# LV_Power.net
KiCad netlist of a schematic drawn in Altium Designer
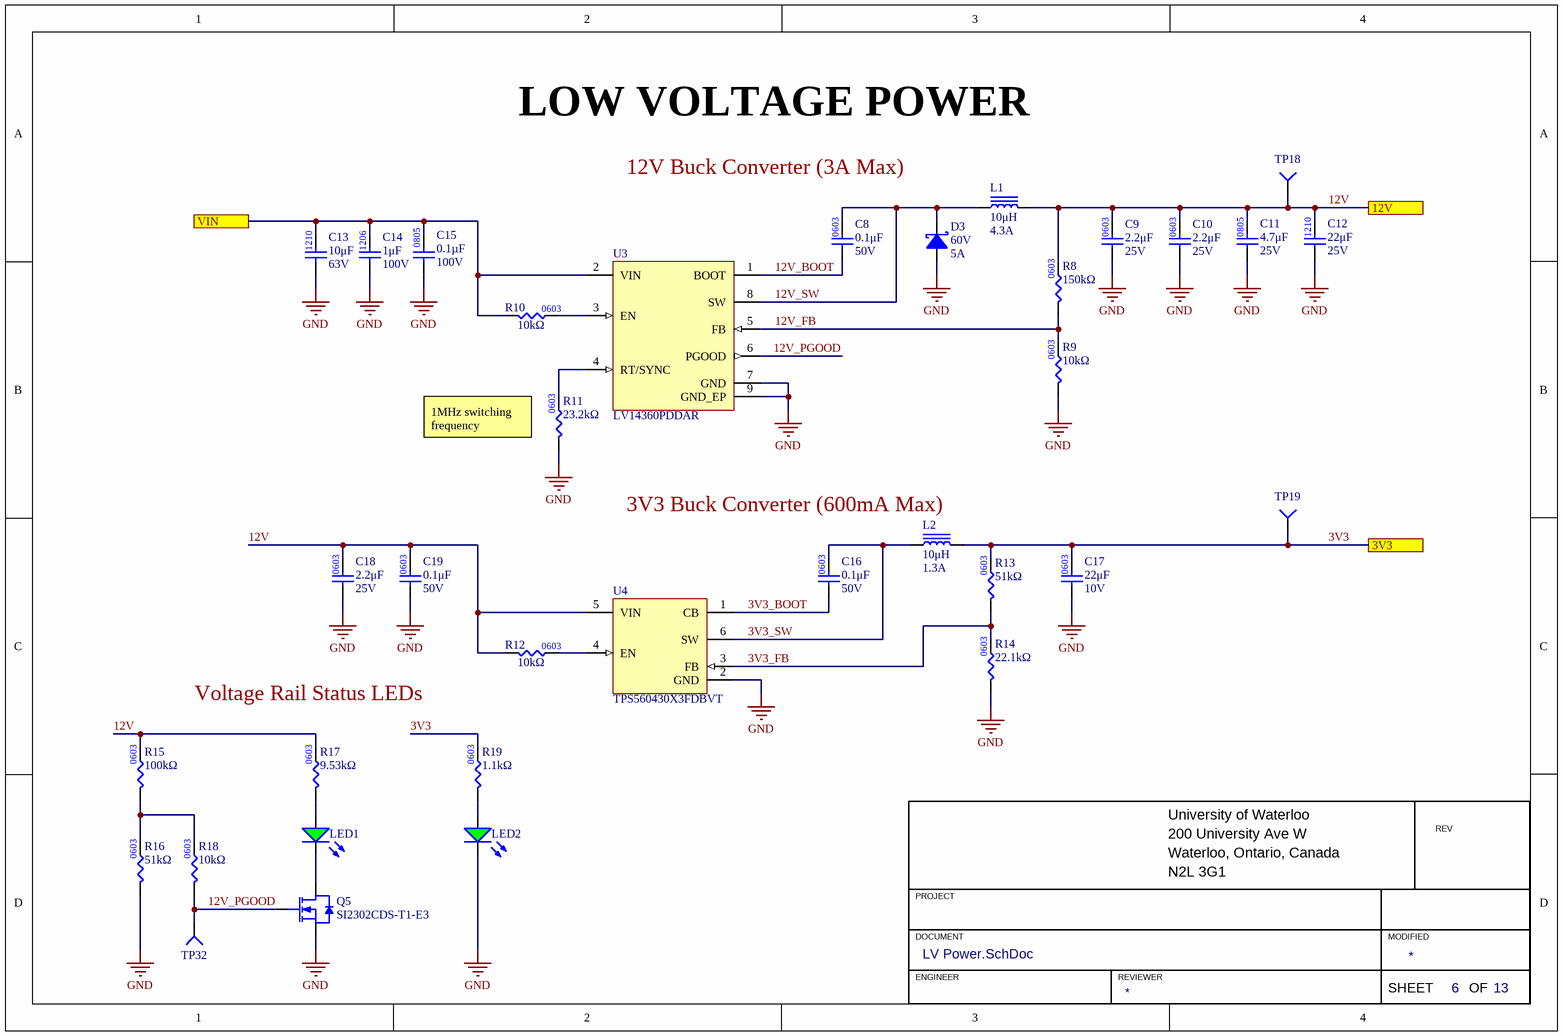
[diagram p0: LV Power.SchDoc]

(export (version "E")
  (design (tool "Eeschema 10.0.6"))
  (components
    (comp (ref "C8")
      (value "0.1μF")
      (footprint "CAP0603")
      (description "CAP CER 0.1UF 50V X7R 0603")
      (fields (field (name "VOLTAGE RATING") "50V") (field (name "Comment") "CAP_0.1uF_50V_0603"))
      (libsource (lib "Personal_Schematic_Library_2022") (part "CAP_0.1uF_50V_0603"))
    )
    (comp (ref "C9")
      (value "2.2μF")
      (footprint "CAP0603")
      (description "CAP CER 2.2UF 25V X5R 0603")
      (fields (field (name "VOLTAGE RATING") "25V") (field (name "Comment") "CAP_2.2uF_25V_0603"))
      (libsource (lib "Personal_Schematic_Library_2022") (part "CAP_2.2uF_25V_0603"))
    )
    (comp (ref "C10")
      (value "2.2μF")
      (footprint "CAP0603")
      (description "CAP CER 2.2UF 25V X5R 0603")
      (fields (field (name "VOLTAGE RATING") "25V") (field (name "Comment") "CAP_2.2uF_25V_0603"))
      (libsource (lib "Personal_Schematic_Library_2022") (part "CAP_2.2uF_25V_0603"))
    )
    (comp (ref "C11")
      (value "4.7μF")
      (footprint "CAP0805")
      (description "CAP CER 4.7UF 25V X7R 0805")
      (fields (field (name "VOLTAGE RATING") "25V") (field (name "Comment") "CAP_4.7uF_25V_0805"))
      (libsource (lib "Personal_Schematic_Library_2022") (part "CAP_4.7uF_25V_0805"))
    )
    (comp (ref "C12")
      (value "22μF")
      (footprint "CAP1210")
      (description "CAP CER 22UF 25V X7R 1210")
      (fields (field (name "VOLTAGE RATING") "25V") (field (name "Comment") "CAP_22uF_25V_1210"))
      (libsource (lib "Personal_Schematic_Library_2022") (part "CAP_22uF_25V_1210"))
    )
    (comp (ref "C13")
      (value "10μF")
      (footprint "CAP1210")
      (description "CAP CER 10UF 63V X7R 1210")
      (fields (field (name "VOLTAGE RATING") "63V") (field (name "Comment") "CAP_10uF_63V_1210"))
      (libsource (lib "Personal_Schematic_Library_2022") (part "CAP_10uF_63V_1210"))
    )
    (comp (ref "C14")
      (value "1μF")
      (footprint "CAP1206")
      (description "CAP CER 1UF 100V X7R 1206")
      (fields (field (name "VOLTAGE RATING") "100V") (field (name "Comment") "CAP_1uF_100V_1206"))
      (libsource (lib "Personal_Schematic_Library_2022") (part "CAP_1uF_100V_1206"))
    )
    (comp (ref "C15")
      (value "0.1µF")
      (footprint "CAP0805")
      (description "CAP CER 0.1UF 100V X7R 0805")
      (fields (field (name "VOLTAGE RATING") "100V") (field (name "Comment") "CAP_0.1uF_100V_0805"))
      (libsource (lib "Personal_Schematic_Library_2022") (part "CAP_0.1uF_100V_0805"))
    )
    (comp (ref "C16")
      (value "0.1μF")
      (footprint "CAP0603")
      (description "CAP CER 0.1UF 50V X7R 0603")
      (fields (field (name "VOLTAGE RATING") "50V") (field (name "Comment") "CAP_0.1uF_50V_0603"))
      (libsource (lib "Personal_Schematic_Library_2022") (part "CAP_0.1uF_50V_0603"))
    )
    (comp (ref "C17")
      (value "22μF")
      (footprint "CAP0603")
      (description "CAP CER 22UF 10V X5R 0603")
      (fields
        (field (name "MANUFACTURER") "Taiyo Yuden")
        (field (name "MANUFACTURER PART NUMBER") "LMK107BBJ226MA-T")
        (field (name "VOLTAGE RATING") "10V")
      )
      (libsource (lib "Personal_Schematic_Library_2022") (part "CAP_22uF_10V_0603"))
    )
    (comp (ref "C18")
      (value "2.2μF")
      (footprint "CAP0603")
      (description "CAP CER 2.2UF 25V X5R 0603")
      (fields (field (name "VOLTAGE RATING") "25V") (field (name "Comment") "CAP_2.2uF_25V_0603"))
      (libsource (lib "Personal_Schematic_Library_2022") (part "CAP_2.2uF_25V_0603"))
    )
    (comp (ref "C19")
      (value "0.1μF")
      (footprint "CAP0603")
      (description "CAP CER 0.1UF 50V X7R 0603")
      (fields (field (name "VOLTAGE RATING") "50V") (field (name "Comment") "CAP_0.1uF_50V_0603"))
      (libsource (lib "Personal_Schematic_Library_2022") (part "CAP_0.1uF_50V_0603"))
    )
    (comp (ref "D3")
      (value "DIO_SCHOTTKY_60V_5A")
      (footprint "DIO-INC_SMA")
      (description "DIODE SCHOTTKY 60V 5A SMA")
      (fields (field (name "VR (MAX)") "60V") (field (name "CURRENT - AVERAGE RECTIFIED (IO)") "5A"))
      (libsource (lib "Personal_Schematic_Library_2022") (part "DIO_SCHOTTKY_60V_5A"))
    )
    (comp (ref "L1")
      (value "10μH")
      (footprint "IND_MURATA_DS106C2")
      (description "FIXED IND 10UH 4.3A 28 MOHM SMD")
      (fields (field (name "CURRENT RATING") "4.3A") (field (name "Comment") "IND_10uH_4.3A"))
      (libsource (lib "Personal_Schematic_Library_2022") (part "IND_10uH_4.3A"))
    )
    (comp (ref "L2")
      (value "10μH")
      (footprint "IND_ABRACON_ASPI4030S")
      (description "FIXED IND 12UH 1.3A 135 MOHM SMD")
      (fields (field (name "CURRENT RATING") "1.3A") (field (name "Comment") "IND_10uH_1.3A"))
      (libsource (lib "Personal_Schematic_Library_2022") (part "IND_10uH_1.3A"))
    )
    (comp (ref "LED1")
      (value "LED_GREEN_0805")
      (footprint "LED_0805_GREEN")
      (description "LED GREEN DIFFUSED 0805 SMD")
      (libsource (lib "Personal_Schematic_Library_2022") (part "LED_GREEN_0805"))
    )
    (comp (ref "LED2")
      (value "LED_GREEN_0805")
      (footprint "LED_0805_GREEN")
      (description "LED GREEN DIFFUSED 0805 SMD")
      (libsource (lib "Personal_Schematic_Library_2022") (part "LED_GREEN_0805"))
    )
    (comp (ref "Q5")
      (value "NMOS_20V_6A")
      (footprint "SOT23-3")
      (description "MOSFET N-CH 20V 2.6A SOT23-3")
      (fields (field (name "MANUFACTURER PART NUMBER 1") "SI2302CDS-T1-E3"))
      (libsource (lib "Personal_Schematic_Library_2022") (part "NMOS_20V_2.6A"))
    )
    (comp (ref "R8")
      (value "150kΩ")
      (footprint "RES0603")
      (description "RES 150K OHM 1% 1/10W 0603")
      (fields (field (name "Comment") "RES_150kΩ_0603_1%"))
      (libsource (lib "Personal_Schematic_Library_2022") (part "RES_150kΩ_0603_1%"))
    )
    (comp (ref "R9")
      (value "10kΩ")
      (footprint "RES0603")
      (description "RES 10K OHM 1% 1/8W 0603")
      (fields (field (name "Comment") "RES_10kΩ_0603_1%"))
      (libsource (lib "Personal_Schematic_Library_2022") (part "RES_10kΩ_0603_1%"))
    )
    (comp (ref "R10")
      (value "10kΩ")
      (footprint "RES0603")
      (description "RES 10K OHM 1% 1/8W 0603")
      (fields (field (name "Comment") "RES_10kΩ_0603_1%"))
      (libsource (lib "Personal_Schematic_Library_2022") (part "RES_10kΩ_0603_1%"))
    )
    (comp (ref "R11")
      (value "23.2kΩ")
      (footprint "RES0603")
      (description "RES 23.2K OHM 1% 1/10W 0603")
      (fields (field (name "Comment") "RES_23.2kΩ_0603_1%"))
      (libsource (lib "Personal_Schematic_Library_2022") (part "RES_23.2kΩ_0603_1%"))
    )
    (comp (ref "R12")
      (value "10kΩ")
      (footprint "RES0603")
      (description "RES 10K OHM 1% 1/8W 0603")
      (fields (field (name "Comment") "RES_10kΩ_0603_1%"))
      (libsource (lib "Personal_Schematic_Library_2022") (part "RES_10kΩ_0603_1%"))
    )
    (comp (ref "R13")
      (value "51kΩ")
      (footprint "RES0603")
      (description "RES 51K OHM 1% 1/10W 0603")
      (fields (field (name "Comment") "RES_51kΩ_0603_1%"))
      (libsource (lib "Personal_Schematic_Library_2022") (part "RES_51kΩ_0603_1%"))
    )
    (comp (ref "R14")
      (value "22.1kΩ")
      (footprint "RES0603")
      (description "RES 22.1K OHM 1% 1/10W 0603")
      (fields (field (name "Comment") "RES_22.1kΩ_0603_1%"))
      (libsource (lib "Personal_Schematic_Library_2022") (part "RES_22.1kΩ_0603_1%"))
    )
    (comp (ref "R15")
      (value "100kΩ")
      (footprint "RES0603")
      (description "RES 100K OHM 1% 1/10W 0603")
      (fields (field (name "Comment") "RES_100kΩ_0603_1%"))
      (libsource (lib "Personal_Schematic_Library_2022") (part "RES_100kΩ_0603_1%"))
    )
    (comp (ref "R16")
      (value "51kΩ")
      (footprint "RES0603")
      (description "RES 51K OHM 1% 1/10W 0603")
      (fields (field (name "Comment") "RES_51kΩ_0603_1%"))
      (libsource (lib "Personal_Schematic_Library_2022") (part "RES_51kΩ_0603_1%"))
    )
    (comp (ref "R17")
      (value "9.53kΩ")
      (footprint "RES0603")
      (description "RES 9.53K OHM 1% 1/10W 0603")
      (fields (field (name "Comment") "RES_9.53kΩ_0603_1%"))
      (libsource (lib "Personal_Schematic_Library_2022") (part "RES_9.53kΩ_0603_1%"))
    )
    (comp (ref "R18")
      (value "10kΩ")
      (footprint "RES0603")
      (description "RES 10K OHM 1% 1/8W 0603")
      (fields (field (name "Comment") "RES_10kΩ_0603_1%"))
      (libsource (lib "Personal_Schematic_Library_2022") (part "RES_10kΩ_0603_1%"))
    )
    (comp (ref "R19")
      (value "1.1kΩ")
      (footprint "RES0603")
      (description "RES 1.1K OHM 1% 1/10W 0603")
      (fields (field (name "Comment") "RES_1.1kΩ_0603_1%"))
      (libsource (lib "Personal_Schematic_Library_2022") (part "RES_1.1kΩ_0603_1%"))
    )
    (comp (ref "TP18")
      (value "TESTPOINT_KEYSTONE_LOOP")
      (footprint "KEYSTONE_5019")
      (description "PC TEST POINT MINIATURE")
      (libsource (lib "Personal_Schematic_Library_2022") (part "TESTPOINT_KEYSTONE_LOOP"))
    )
    (comp (ref "TP19")
      (value "TESTPOINT_KEYSTONE_LOOP")
      (footprint "KEYSTONE_5019")
      (description "PC TEST POINT MINIATURE")
      (libsource (lib "Personal_Schematic_Library_2022") (part "TESTPOINT_KEYSTONE_LOOP"))
    )
    (comp (ref "TP32")
      (value "TESTPOINT_1MM_CIRCLE")
      (footprint "TESTPOINT_CIRCLE_1MM")
      (description "TESTPOINT 1MM CIRCLE")
      (libsource (lib "Personal_Schematic_Library_2022") (part "TESTPOINT_1MM_CIRCLE"))
    )
    (comp (ref "U3")
      (value "LV14360PDDAR")
      (footprint "TI_8-PowerPad-SOIC")
      (description "IC REG BUCK ADJ 3A 8SOPWR")
      (libsource (lib "Personal_Schematic_Library_2022") (part "LV14360PDDAR"))
    )
    (comp (ref "U4")
      (value "TPS560430X3FDBVT")
      (footprint "SOT23-6")
      (description "IC REG BUCK 3.3V 600MA SOT23-6")
      (libsource (lib "Personal_Schematic_Library_2022") (part "TPS560430X3FDBVT"))
    )
  )
  (nets
    (net (code "1") (name "/3V3") (class "Default")
      (node (ref "C17") (pin "2") (pinfunction "2_2") (pintype "passive"))
      (node (ref "L2") (pin "2") (pinfunction "2_2") (pintype "passive"))
      (node (ref "R13") (pin "2") (pinfunction "2_2") (pintype "passive"))
      (node (ref "R19") (pin "2") (pinfunction "2_2") (pintype "passive"))
      (node (ref "TP19") (pin "1") (pinfunction "=value_1") (pintype "passive"))
    )
    (net (code "2") (name "/3V3_BOOT") (class "Default")
      (node (ref "C16") (pin "1") (pinfunction "1_1") (pintype "passive"))
      (node (ref "U4") (pin "1") (pinfunction "CB_1") (pintype "power_in"))
    )
    (net (code "3") (name "/3V3_FB") (class "Default")
      (node (ref "R13") (pin "1") (pinfunction "1_1") (pintype "passive"))
      (node (ref "R14") (pin "2") (pinfunction "2_2") (pintype "passive"))
      (node (ref "U4") (pin "3") (pinfunction "FB_3") (pintype "input"))
    )
    (net (code "4") (name "/3V3_SW") (class "Default")
      (node (ref "C16") (pin "2") (pinfunction "2_2") (pintype "passive"))
      (node (ref "L2") (pin "1") (pinfunction "1_1") (pintype "passive"))
      (node (ref "U4") (pin "6") (pinfunction "SW_6") (pintype "power_in"))
    )
    (net (code "5") (name "/12V") (class "Default")
      (node (ref "C10") (pin "2") (pinfunction "2_2") (pintype "passive"))
      (node (ref "C11") (pin "2") (pinfunction "2_2") (pintype "passive"))
      (node (ref "C12") (pin "2") (pinfunction "2_2") (pintype "passive"))
      (node (ref "C18") (pin "2") (pinfunction "2_2") (pintype "passive"))
      (node (ref "C19") (pin "2") (pinfunction "2_2") (pintype "passive"))
      (node (ref "C9") (pin "2") (pinfunction "2_2") (pintype "passive"))
      (node (ref "L1") (pin "2") (pinfunction "2_2") (pintype "passive"))
      (node (ref "R12") (pin "1") (pinfunction "1_1") (pintype "passive"))
      (node (ref "R15") (pin "2") (pinfunction "2_2") (pintype "passive"))
      (node (ref "R17") (pin "2") (pinfunction "2_2") (pintype "passive"))
      (node (ref "R8") (pin "2") (pinfunction "2_2") (pintype "passive"))
      (node (ref "TP18") (pin "1") (pinfunction "=value_1") (pintype "passive"))
      (node (ref "U4") (pin "5") (pinfunction "VIN_5") (pintype "power_in"))
    )
    (net (code "6") (name "/12V_BOOT") (class "Default")
      (node (ref "C8") (pin "1") (pinfunction "1_1") (pintype "passive"))
      (node (ref "U3") (pin "1") (pinfunction "BOOT_1") (pintype "power_in"))
    )
    (net (code "7") (name "/12V_FB") (class "Default")
      (node (ref "R8") (pin "1") (pinfunction "1_1") (pintype "passive"))
      (node (ref "R9") (pin "2") (pinfunction "2_2") (pintype "passive"))
      (node (ref "U3") (pin "5") (pinfunction "FB_5") (pintype "input"))
    )
    (net (code "8") (name "/12V_PGOOD") (class "Default")
      (node (ref "Q5") (pin "1") (pinfunction "GATE_1") (pintype "passive"))
      (node (ref "R18") (pin "1") (pinfunction "1_1") (pintype "passive"))
      (node (ref "TP32") (pin "1") (pinfunction "=value_1") (pintype "passive"))
      (node (ref "U3") (pin "6") (pinfunction "PGOOD_6") (pintype "output"))
    )
    (net (code "9") (name "/12V_SW") (class "Default")
      (node (ref "C8") (pin "2") (pinfunction "2_2") (pintype "passive"))
      (node (ref "D3") (pin "1") (pinfunction "Cathode_1") (pintype "passive"))
      (node (ref "L1") (pin "1") (pinfunction "1_1") (pintype "passive"))
      (node (ref "U3") (pin "8") (pinfunction "SW_8") (pintype "power_in"))
    )
    (net (code "10") (name "/VIN") (class "Default")
      (node (ref "C13") (pin "2") (pinfunction "2_2") (pintype "passive"))
      (node (ref "C14") (pin "2") (pinfunction "2_2") (pintype "passive"))
      (node (ref "C15") (pin "2") (pinfunction "2_2") (pintype "passive"))
      (node (ref "R10") (pin "1") (pinfunction "1_1") (pintype "passive"))
      (node (ref "U3") (pin "2") (pinfunction "VIN_2") (pintype "power_in"))
    )
    (net (code "11") (name "GND") (class "Default")
      (node (ref "C10") (pin "1") (pinfunction "1_1") (pintype "passive"))
      (node (ref "C11") (pin "1") (pinfunction "1_1") (pintype "passive"))
      (node (ref "C12") (pin "1") (pinfunction "1_1") (pintype "passive"))
      (node (ref "C13") (pin "1") (pinfunction "1_1") (pintype "passive"))
      (node (ref "C14") (pin "1") (pinfunction "1_1") (pintype "passive"))
      (node (ref "C15") (pin "1") (pinfunction "1_1") (pintype "passive"))
      (node (ref "C17") (pin "1") (pinfunction "1_1") (pintype "passive"))
      (node (ref "C18") (pin "1") (pinfunction "1_1") (pintype "passive"))
      (node (ref "C19") (pin "1") (pinfunction "1_1") (pintype "passive"))
      (node (ref "C9") (pin "1") (pinfunction "1_1") (pintype "passive"))
      (node (ref "D3") (pin "2") (pinfunction "Anode_2") (pintype "passive"))
      (node (ref "LED2") (pin "2") (pinfunction "K_2") (pintype "passive"))
      (node (ref "Q5") (pin "2") (pinfunction "SOURCE_2") (pintype "passive"))
      (node (ref "R11") (pin "1") (pinfunction "1_1") (pintype "passive"))
      (node (ref "R14") (pin "1") (pinfunction "1_1") (pintype "passive"))
      (node (ref "R16") (pin "1") (pinfunction "1_1") (pintype "passive"))
      (node (ref "R9") (pin "1") (pinfunction "1_1") (pintype "passive"))
      (node (ref "U3") (pin "7") (pinfunction "GND_7") (pintype "power_in"))
      (node (ref "U3") (pin "9") (pinfunction "GND_EP_9") (pintype "power_in"))
      (node (ref "U4") (pin "2") (pinfunction "GND_2") (pintype "power_in"))
    )
    (net (code "12") (name "Net-(LED1-A)") (class "Default")
      (node (ref "LED1") (pin "1") (pinfunction "A_1") (pintype "passive"))
      (node (ref "R17") (pin "1") (pinfunction "1_1") (pintype "passive"))
    )
    (net (code "13") (name "Net-(LED1-K)") (class "Default")
      (node (ref "LED1") (pin "2") (pinfunction "K_2") (pintype "passive"))
      (node (ref "Q5") (pin "3") (pinfunction "DRAIN_3") (pintype "passive"))
    )
    (net (code "14") (name "Net-(LED2-A)") (class "Default")
      (node (ref "LED2") (pin "1") (pinfunction "A_1") (pintype "passive"))
      (node (ref "R19") (pin "1") (pinfunction "1_1") (pintype "passive"))
    )
    (net (code "15") (name "Net-(R15-Pad1)") (class "Default")
      (node (ref "R15") (pin "1") (pinfunction "1_1") (pintype "passive"))
      (node (ref "R16") (pin "2") (pinfunction "2_2") (pintype "passive"))
      (node (ref "R18") (pin "2") (pinfunction "2_2") (pintype "passive"))
    )
    (net (code "16") (name "Net-(U3-EN)") (class "Default")
      (node (ref "R10") (pin "2") (pinfunction "2_2") (pintype "passive"))
      (node (ref "U3") (pin "3") (pinfunction "EN_3") (pintype "input"))
    )
    (net (code "17") (name "Net-(U3-RT{slash}SYNC)") (class "Default")
      (node (ref "R11") (pin "2") (pinfunction "2_2") (pintype "passive"))
      (node (ref "U3") (pin "4") (pinfunction "RT/SYNC_4") (pintype "input"))
    )
    (net (code "18") (name "Net-(U4-EN)") (class "Default")
      (node (ref "R12") (pin "2") (pinfunction "2_2") (pintype "passive"))
      (node (ref "U4") (pin "4") (pinfunction "EN_4") (pintype "input"))
    )
  )
)
